# NE555-PWM.net
KiCad netlist of a schematic drawn in Altium Designer
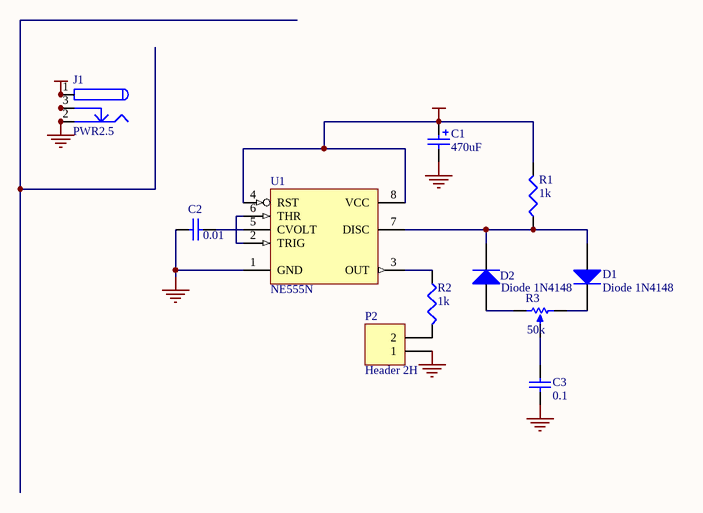
[diagram p0: NE555-PWM.SCHDOC]

(export (version "E")
  (design (tool "Eeschema 10.0.6"))
  (components
    (comp (ref "C1")
      (value "470uF")
      (footprint "POLAR0.8")
      (description "Polarized Capacitor (Axial)")
      (fields (field (name "PUBLISHER") "Altium Limited"))
      (libsource (lib "Miscellaneous Devices") (part "Cap Pol2"))
    )
    (comp (ref "C2")
      (value "0.01")
      (footprint "CC3216-1206")
      (description "Capacitor (Semiconductor SIM Model)")
      (fields (field (name "PUBLISHER") "Altium Limited"))
      (libsource (lib "Miscellaneous Devices") (part "Cap Semi"))
    )
    (comp (ref "C3")
      (value "0.1")
      (footprint "CC3216-1206")
      (description "Capacitor (Semiconductor SIM Model)")
      (fields (field (name "PUBLISHER") "Altium Limited"))
      (libsource (lib "Miscellaneous Devices") (part "Cap Semi"))
    )
    (comp (ref "D1")
      (value "Diode 1N4148")
      (footprint "DIO7.1-3.9x1.9")
      (description "High Conductance Fast Diode")
      (fields (field (name "PUBLISHER") "Altium Limited"))
      (libsource (lib "Miscellaneous Devices") (part "Diode 1N4148"))
    )
    (comp (ref "D2")
      (value "Diode 1N4148")
      (footprint "DIO7.1-3.9x1.9")
      (description "High Conductance Fast Diode")
      (fields (field (name "PUBLISHER") "Altium Limited"))
      (libsource (lib "Miscellaneous Devices") (part "Diode 1N4148"))
    )
    (comp (ref "J1")
      (value "PWR2.5")
      (footprint "KLD-0202")
      (description "Low Voltage Power Supply Connector")
      (fields (field (name "PUBLISHER") "Altium Limited"))
      (libsource (lib "Miscellaneous Connectors") (part "PWR2.5"))
    )
    (comp (ref "P2")
      (value "Header 2H")
      (footprint "HDR1X2H")
      (description "Header, 2-Pin, Right Angle")
      (fields (field (name "PUBLISHER") "Altium Limited"))
      (libsource (lib "Miscellaneous Connectors") (part "Header 2H"))
    )
    (comp (ref "R1")
      (value "1k")
      (footprint "CR1608-0603")
      (description "Resistor")
      (fields (field (name "PUBLISHER") "Altium Limited"))
      (libsource (lib "Miscellaneous Devices") (part "Res3"))
    )
    (comp (ref "R2")
      (value "1k")
      (footprint "CR1608-0603")
      (description "Resistor")
      (fields (field (name "PUBLISHER") "Altium Limited"))
      (libsource (lib "Miscellaneous Devices") (part "Res3"))
    )
    (comp (ref "R3")
      (value "50k")
      (footprint "VR5")
      (description "Potentiometer")
      (fields (field (name "PUBLISHER") "Altium Limited"))
      (libsource (lib "Miscellaneous Devices") (part "RPot"))
    )
    (comp (ref "U1")
      (value "NE555N")
      (footprint "DIP8")
      (description "General-Purpose Single Bipolar Timer")
      (fields (field (name "PUBLISHER") "Altium Limited"))
      (libsource (lib "ST Analog Timer Circuit") (part "NE555N"))
    )
  )
  (nets
    (net (code "1") (name "+5") (class "Default")
      (node (ref "C1") (pin "1") (pinfunction "1_1") (pintype "passive"))
      (node (ref "J1") (pin "1") (pinfunction "1_1") (pintype "power_in"))
      (node (ref "J1") (pin "1A") (pinfunction "1A_1A") (pintype "power_in"))
      (node (ref "J1") (pin "1B") (pinfunction "1B_1B") (pintype "power_in"))
      (node (ref "R1") (pin "2") (pinfunction "2_2") (pintype "passive"))
      (node (ref "U1") (pin "4") (pinfunction "RST_4") (pintype "input"))
      (node (ref "U1") (pin "8") (pinfunction "VCC_8") (pintype "power_in"))
    )
    (net (code "2") (name "GND") (class "Default")
      (node (ref "C1") (pin "2") (pinfunction "2_2") (pintype "passive"))
      (node (ref "C2") (pin "2") (pinfunction "2_2") (pintype "passive"))
      (node (ref "C3") (pin "1") (pinfunction "1_1") (pintype "passive"))
      (node (ref "J1") (pin "2") (pinfunction "2_2") (pintype "power_in"))
      (node (ref "J1") (pin "2A") (pinfunction "2A_2A") (pintype "power_in"))
      (node (ref "J1") (pin "2B") (pinfunction "2B_2B") (pintype "power_in"))
      (node (ref "P2") (pin "1") (pinfunction "1_1") (pintype "passive"))
      (node (ref "U1") (pin "1") (pinfunction "GND_1") (pintype "power_in"))
    )
    (net (code "3") (name "Net-(D1-A)") (class "Default")
      (node (ref "D1") (pin "1") (pinfunction "A_1") (pintype "passive"))
      (node (ref "D2") (pin "2") (pinfunction "K_2") (pintype "passive"))
      (node (ref "R1") (pin "1") (pinfunction "1_1") (pintype "passive"))
      (node (ref "U1") (pin "7") (pinfunction "DISC_7") (pintype "open_collector"))
    )
    (net (code "4") (name "Net-(D1-K)") (class "Default")
      (node (ref "D1") (pin "2") (pinfunction "K_2") (pintype "passive"))
      (node (ref "R3") (pin "2") (pinfunction "BOT_2") (pintype "passive"))
    )
    (net (code "5") (name "Net-(D2-A)") (class "Default")
      (node (ref "D2") (pin "1") (pinfunction "A_1") (pintype "passive"))
      (node (ref "R3") (pin "1") (pinfunction "TOP_1") (pintype "passive"))
    )
    (net (code "6") (name "Net-(J1-Pad3)") (class "Default")
      (node (ref "J1") (pin "3") (pinfunction "3_3") (pintype "power_in"))
      (node (ref "J1") (pin "3A") (pinfunction "3A_3A") (pintype "power_in"))
      (node (ref "J1") (pin "3B") (pinfunction "3B_3B") (pintype "power_in"))
    )
    (net (code "7") (name "Net-(P2-Pad2)") (class "Default")
      (node (ref "P2") (pin "2") (pinfunction "2_2") (pintype "passive"))
      (node (ref "R2") (pin "2") (pinfunction "2_2") (pintype "passive"))
    )
    (net (code "8") (name "Net-(R3-TAP)") (class "Default")
      (node (ref "C3") (pin "2") (pinfunction "2_2") (pintype "passive"))
      (node (ref "R3") (pin "3") (pinfunction "TAP_3") (pintype "passive"))
    )
    (net (code "9") (name "Net-(U1-CVOLT)") (class "Default")
      (node (ref "C2") (pin "1") (pinfunction "1_1") (pintype "passive"))
      (node (ref "U1") (pin "5") (pinfunction "CVOLT_5") (pintype "passive"))
    )
    (net (code "10") (name "Net-(U1-OUT)") (class "Default")
      (node (ref "R2") (pin "1") (pinfunction "1_1") (pintype "passive"))
      (node (ref "U1") (pin "3") (pinfunction "OUT_3") (pintype "output"))
    )
    (net (code "11") (name "Net-(U1-THR)") (class "Default")
      (node (ref "U1") (pin "2") (pinfunction "TRIG_2") (pintype "input"))
      (node (ref "U1") (pin "6") (pinfunction "THR_6") (pintype "input"))
    )
  )
)
